# agent-mother.net
KiCad netlist of a schematic drawn in Altium Designer
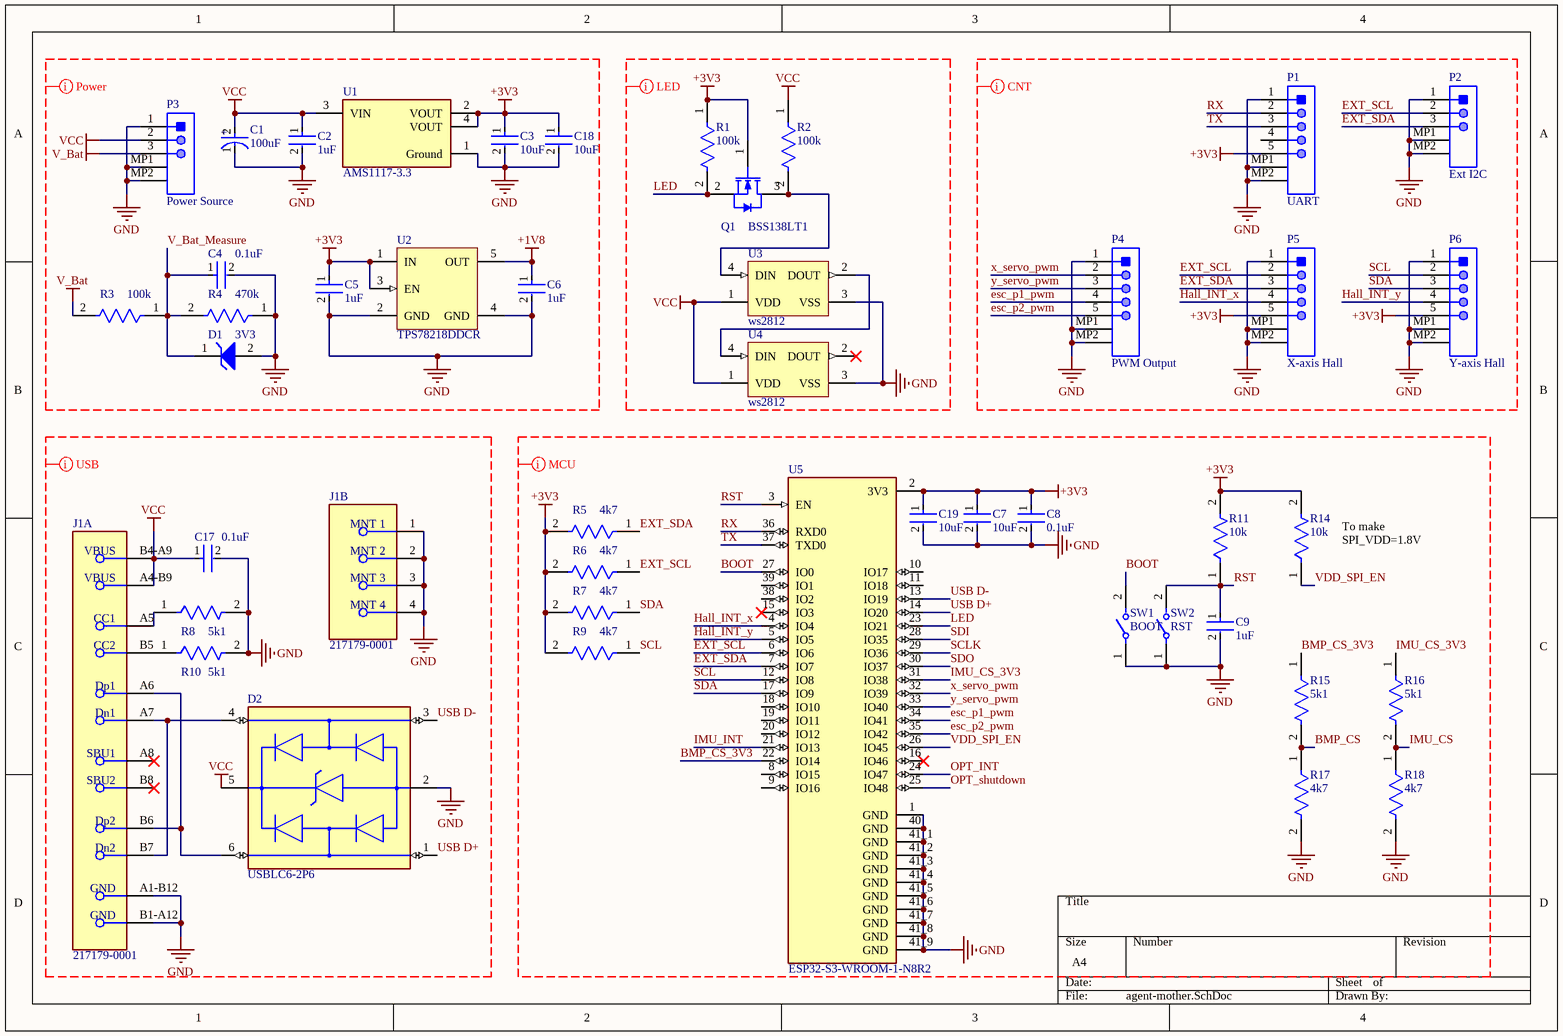
[diagram p0: agent-mother.SchDoc]

(export (version "E")
  (design (tool "Eeschema 10.0.6"))
  (components
    (comp (ref "C1")
      (value "100uF")
      (footprint "FP-T495D107K016ATE125-MFG")
      (description "CAP TANT 100UF 10% 16V 2917")
      (fields (field (name "VOLTAGE") "16V") (field (name "TOLERANCE") "10%"))
      (libsource (lib "Altium Content Vault") (part "a00bbbee19879c290e62620ae7e47b1"))
    )
    (comp (ref "C2")
      (value "1uF")
      (footprint "FP-C0402-BB-MFG")
      (description "CAP CER 1uF 16V X7R 0402")
      (fields
        (field (name "TOLERANCE") "0.1")
        (field (name "OCTOPART") "https://octopart.com/c0402c104k4ractu-kemet-94158")
      )
      (libsource (lib "Altium Content Vault") (part "b4654b650e69147ec39a6b967a45e02"))
    )
    (comp (ref "C3")
      (value "10uF")
      (footprint "FP-C0402-BB-MFG")
      (description "CAP CER 22uF 16V X7R 0402")
      (fields
        (field (name "TOLERANCE") "0.1")
        (field (name "OCTOPART") "https://octopart.com/c0402c104k4ractu-kemet-94158")
      )
      (libsource (lib "Altium Content Vault") (part "b4654b650e69147ec39a6b967a45e02"))
    )
    (comp (ref "C4")
      (value "0.1uF")
      (footprint "FP-C0402-BB-MFG")
      (description "CAP CER 0.1uF 16V X7R 0402")
      (fields
        (field (name "TOLERANCE") "0.1")
        (field (name "OCTOPART") "https://octopart.com/c0402c104k4ractu-kemet-94158")
      )
      (libsource (lib "Altium Content Vault") (part "b4654b650e69147ec39a6b967a45e02"))
    )
    (comp (ref "C5")
      (value "1uF")
      (footprint "FP-C0402-BB-MFG")
      (description "CAP CER 1uF 16V X7R 0402")
      (fields
        (field (name "TOLERANCE") "0.1")
        (field (name "OCTOPART") "https://octopart.com/c0402c104k4ractu-kemet-94158")
      )
      (libsource (lib "Altium Content Vault") (part "b4654b650e69147ec39a6b967a45e02"))
    )
    (comp (ref "C6")
      (value "1uF")
      (footprint "FP-C0402-BB-MFG")
      (description "CAP CER 1uF 16V X7R 0402")
      (fields
        (field (name "TOLERANCE") "0.1")
        (field (name "OCTOPART") "https://octopart.com/c0402c104k4ractu-kemet-94158")
      )
      (libsource (lib "Altium Content Vault") (part "b4654b650e69147ec39a6b967a45e02"))
    )
    (comp (ref "C7")
      (value "10uF")
      (footprint "FP-C0402-BB-MFG")
      (description "CAP CER 22uF 16V X7R 0402")
      (fields
        (field (name "TOLERANCE") "0.1")
        (field (name "OCTOPART") "https://octopart.com/c0402c104k4ractu-kemet-94158")
      )
      (libsource (lib "Altium Content Vault") (part "b4654b650e69147ec39a6b967a45e02"))
    )
    (comp (ref "C8")
      (value "0.1uF")
      (footprint "FP-C0402-BB-MFG")
      (description "CAP CER 0.1uF 16V X7R 0402")
      (fields
        (field (name "TOLERANCE") "0.1")
        (field (name "OCTOPART") "https://octopart.com/c0402c104k4ractu-kemet-94158")
      )
      (libsource (lib "Altium Content Vault") (part "b4654b650e69147ec39a6b967a45e02"))
    )
    (comp (ref "C9")
      (value "1uF")
      (footprint "FP-C0402-BB-MFG")
      (description "CAP CER 1uF 16V X7R 0402")
      (fields
        (field (name "TOLERANCE") "0.1")
        (field (name "OCTOPART") "https://octopart.com/c0402c104k4ractu-kemet-94158")
      )
      (libsource (lib "Altium Content Vault") (part "b4654b650e69147ec39a6b967a45e02"))
    )
    (comp (ref "C17")
      (value "0.1uF")
      (footprint "FP-C0402-BB-MFG")
      (description "CAP CER 0.1uF 16V X7R 0402")
      (fields
        (field (name "TOLERANCE") "0.1")
        (field (name "OCTOPART") "https://octopart.com/c0402c104k4ractu-kemet-94158")
      )
      (libsource (lib "Altium Content Vault") (part "b4654b650e69147ec39a6b967a45e02"))
    )
    (comp (ref "C18")
      (value "10uF")
      (footprint "FP-C0402-BB-MFG")
      (description "CAP CER 22uF 16V X7R 0402")
      (fields
        (field (name "TOLERANCE") "0.1")
        (field (name "OCTOPART") "https://octopart.com/c0402c104k4ractu-kemet-94158")
      )
      (libsource (lib "Altium Content Vault") (part "b4654b650e69147ec39a6b967a45e02"))
    )
    (comp (ref "C19")
      (value "10uF")
      (footprint "FP-C0402-BB-MFG")
      (description "CAP CER 22uF 16V X7R 0402")
      (fields
        (field (name "TOLERANCE") "0.1")
        (field (name "OCTOPART") "https://octopart.com/c0402c104k4ractu-kemet-94158")
      )
      (libsource (lib "Altium Content Vault") (part "b4654b650e69147ec39a6b967a45e02"))
    )
    (comp (ref "D1")
      (value "3V3")
      (footprint "ONSC-SOD-323-2-477-02_V")
      (description "Zener Voltage Regulator, 300 mW, 2-Pin SOD-323, Pb-Free, Tape and Reel")
      (fields (field (name "PARTNUMBER") "MM3Z3V3T1G") (field (name "MANUFACTURER") "On Semiconductor"))
      (libsource (lib "Altium Content Vault") (part "ONSC-K1A2-2"))
    )
    (comp (ref "D2")
      (value "USBLC6-2P6")
      (footprint "SOT-23-6 USBLC6")
      (description "TVS DIODE 5.25V 17V SOT666")
      (libsource (lib "TVMD") (part "USBLC6-2P6"))
    )
    (comp (ref "J1")
      (value "217179-0001")
      (footprint "FP-217179-0001-MFG")
      (description "CONN RCP USB2.0 TYP C 24P SMD RA")
      (libsource (lib "Altium Content Vault") (part "5f86746d156db037abd23105bb3dbc5"))
    )
    (comp (ref "P1")
      (value "UART")
      (footprint "MOLX-52361-0571-5_V")
      (description "Male Header, Pitch 1.25 mm, 1 x 5 Position, Height 3.4 mm, RoHS, Tape and Reel")
      (fields (field (name "MANUFACTURER") "Molex"))
      (libsource (lib "Altium Content Vault") (part "CN-1P-2M-R5"))
    )
    (comp (ref "P2")
      (value "Ext I2C")
      (footprint "FP-53261-0371-MFG")
      (description "CONN HEADER SMD R/A 3POS 1.25MM")
      (fields
        (field (name "MANUFACTURER") "Molex")
        (field (name "OCTOPART") "https://octopart.com/53261-0371-molex-655314")
      )
      (libsource (lib "Components - 19.08.23 - 20.17") (part "CMP-04776-000071-1"))
    )
    (comp (ref "P3")
      (value "Power Source")
      (footprint "FP-53261-0371-MFG")
      (description "CONN HEADER SMD R/A 3POS 1.25MM")
      (fields
        (field (name "MANUFACTURER") "Molex")
        (field (name "OCTOPART") "https://octopart.com/53261-0371-molex-655314")
      )
      (libsource (lib "Components - 19.08.23 - 20.17") (part "CMP-04776-000071-1"))
    )
    (comp (ref "P4")
      (value "PWM Output")
      (footprint "MOLX-52361-0571-5_V")
      (description "Male Header, Pitch 1.25 mm, 1 x 5 Position, Height 3.4 mm, RoHS, Tape and Reel")
      (fields (field (name "MANUFACTURER") "Molex"))
      (libsource (lib "Altium Content Vault") (part "CN-1P-2M-R5"))
    )
    (comp (ref "P5")
      (value "X-axis Hall")
      (footprint "MOLX-52361-0571-5_V")
      (description "Male Header, Pitch 1.25 mm, 1 x 5 Position, Height 3.4 mm, RoHS, Tape and Reel")
      (fields (field (name "MANUFACTURER") "Molex"))
      (libsource (lib "Altium Content Vault") (part "CN-1P-2M-R5"))
    )
    (comp (ref "P6")
      (value "Y-axis Hall")
      (footprint "MOLX-52361-0571-5_V")
      (description "Male Header, Pitch 1.25 mm, 1 x 5 Position, Height 3.4 mm, RoHS, Tape and Reel")
      (fields (field (name "MANUFACTURER") "Molex"))
      (libsource (lib "Altium Content Vault") (part "CN-1P-2M-R5"))
    )
    (comp (ref "Q1")
      (value "BSS138LT1")
      (footprint "ONSC-SOT-23-3-318-08_V")
      (description "Power MOSFET, BSS138LT1, 200 mA, 50 V, N-Channel, 3-Pin SOT-23, Tape and Reel")
      (fields (field (name "MANUFACTURER") "On Semiconductor"))
      (libsource (lib "Altium Content Vault") (part "ONSC-NMOS-G1S2D3-3"))
    )
    (comp (ref "R1")
      (value "100k")
      (footprint "FP-CRCW0402-e3-IPC_A")
      (description "RES Thick Film, 100kΩ, 0.063W, 0402")
      (fields (field (name "TOLERANCE") "5%"))
      (libsource (lib "Altium Content Vault") (part "1029c3af85768c4190bb7ad29bc67b5"))
    )
    (comp (ref "R2")
      (value "100k")
      (footprint "FP-CRCW0402-e3-IPC_A")
      (description "RES Thick Film, 100kΩ, 0.063W, 0402")
      (fields (field (name "TOLERANCE") "5%"))
      (libsource (lib "Altium Content Vault") (part "1029c3af85768c4190bb7ad29bc67b5"))
    )
    (comp (ref "R3")
      (value "100k")
      (footprint "FP-CRCW0402-e3-IPC_A")
      (description "RES Thick Film, 100kΩ, 0.063W, 0402")
      (fields (field (name "TOLERANCE") "5%"))
      (libsource (lib "Altium Content Vault") (part "1029c3af85768c4190bb7ad29bc67b5"))
    )
    (comp (ref "R4")
      (value "470k")
      (footprint "FP-CRCW0402-e3-IPC_A")
      (description "RES Thick Film, 470kΩ, 0.063W, 0402")
      (fields (field (name "TOLERANCE") "5%"))
      (libsource (lib "Altium Content Vault") (part "1029c3af85768c4190bb7ad29bc67b5"))
    )
    (comp (ref "R5")
      (value "4k7")
      (footprint "FP-CRCW0402-e3-IPC_A")
      (description "RES Thick Film, 4k7Ω, 0.063W, 0402")
      (fields (field (name "TOLERANCE") "5%"))
      (libsource (lib "Altium Content Vault") (part "1029c3af85768c4190bb7ad29bc67b5"))
    )
    (comp (ref "R6")
      (value "4k7")
      (footprint "FP-CRCW0402-e3-IPC_A")
      (description "RES Thick Film, 4k7Ω, 0.063W, 0402")
      (fields (field (name "TOLERANCE") "5%"))
      (libsource (lib "Altium Content Vault") (part "1029c3af85768c4190bb7ad29bc67b5"))
    )
    (comp (ref "R7")
      (value "4k7")
      (footprint "FP-CRCW0402-e3-IPC_A")
      (description "RES Thick Film, 4k7Ω, 0.063W, 0402")
      (fields (field (name "TOLERANCE") "5%"))
      (libsource (lib "Altium Content Vault") (part "1029c3af85768c4190bb7ad29bc67b5"))
    )
    (comp (ref "R8")
      (value "5k1")
      (footprint "FP-CRCW0402-e3-IPC_A")
      (description "RES Thick Film, 5k1Ω, 0.063W, 0402")
      (fields (field (name "TOLERANCE") "5%"))
      (libsource (lib "Altium Content Vault") (part "1029c3af85768c4190bb7ad29bc67b5"))
    )
    (comp (ref "R9")
      (value "4k7")
      (footprint "FP-CRCW0402-e3-IPC_A")
      (description "RES Thick Film, 4k7Ω, 0.063W, 0402")
      (fields (field (name "TOLERANCE") "5%"))
      (libsource (lib "Altium Content Vault") (part "1029c3af85768c4190bb7ad29bc67b5"))
    )
    (comp (ref "R10")
      (value "5k1")
      (footprint "FP-CRCW0402-e3-IPC_A")
      (description "RES Thick Film, 5k1Ω, 0.063W, 0402")
      (fields (field (name "TOLERANCE") "5%"))
      (libsource (lib "Altium Content Vault") (part "1029c3af85768c4190bb7ad29bc67b5"))
    )
    (comp (ref "R11")
      (value "10k")
      (footprint "FP-CRCW0402-e3-IPC_A")
      (description "RES Thick Film, 10kΩ, 0.063W, 0402")
      (fields (field (name "TOLERANCE") "5%"))
      (libsource (lib "Altium Content Vault") (part "1029c3af85768c4190bb7ad29bc67b5"))
    )
    (comp (ref "R14")
      (value "10k")
      (footprint "FP-CRCW0402-e3-IPC_A")
      (description "RES Thick Film, 10kΩ, 0.063W, 0402")
      (fields (field (name "TOLERANCE") "5%"))
      (libsource (lib "Altium Content Vault") (part "1029c3af85768c4190bb7ad29bc67b5"))
    )
    (comp (ref "R15")
      (value "5k1")
      (footprint "FP-CRCW0402-e3-IPC_A")
      (description "RES Thick Film, 4k7Ω, 0.063W, 0402")
      (fields (field (name "TOLERANCE") "5%"))
      (libsource (lib "Altium Content Vault") (part "1029c3af85768c4190bb7ad29bc67b5"))
    )
    (comp (ref "R16")
      (value "5k1")
      (footprint "FP-CRCW0402-e3-IPC_A")
      (description "RES Thick Film, 4k7Ω, 0.063W, 0402")
      (fields (field (name "TOLERANCE") "5%"))
      (libsource (lib "Altium Content Vault") (part "1029c3af85768c4190bb7ad29bc67b5"))
    )
    (comp (ref "R17")
      (value "4k7")
      (footprint "FP-CRCW0402-e3-IPC_A")
      (description "RES Thick Film, 4k7Ω, 0.063W, 0402")
      (fields (field (name "TOLERANCE") "5%"))
      (libsource (lib "Altium Content Vault") (part "1029c3af85768c4190bb7ad29bc67b5"))
    )
    (comp (ref "R18")
      (value "4k7")
      (footprint "FP-CRCW0402-e3-IPC_A")
      (description "RES Thick Film, 4k7Ω, 0.063W, 0402")
      (fields (field (name "TOLERANCE") "5%"))
      (libsource (lib "Altium Content Vault") (part "1029c3af85768c4190bb7ad29bc67b5"))
    )
    (comp (ref "SW1")
      (value "BOOT")
      (footprint "FP-B3U-1000P-B-MFG")
      (description "SWITCH TACTILE SPST-NO 0.05A 12V")
      (fields
        (field (name "MANUFACTURER PART NUMBER") "B3U-1000P-B")
        (field (name "OCTOPART") "https://octopart.com/b3u-1000p-b-omron-1057356")
      )
      (libsource (lib "Altium Content Vault") (part "bb27bde45df87f1f469753f287ef5ae"))
    )
    (comp (ref "SW2")
      (value "RST")
      (footprint "FP-B3U-1000P-B-MFG")
      (description "SWITCH TACTILE SPST-NO 0.05A 12V")
      (fields
        (field (name "MANUFACTURER PART NUMBER") "B3U-1000P-B")
        (field (name "OCTOPART") "https://octopart.com/b3u-1000p-b-omron-1057356")
      )
      (libsource (lib "Altium Content Vault") (part "bb27bde45df87f1f469753f287ef5ae"))
    )
    (comp (ref "U1")
      (value "AMS1117-3.3")
      (footprint "FP-AMS1117-IPC_A")
      (description "LDO Voltage Regulators 1A, 3.3V")
      (fields
        (field (name "OCTOPART") "https://octopart.com/ams1117-3.3-advanced+monolithic+systems-25899300")
        (field (name "MANUFACTURER") "Advanced Monolithic Systems")
      )
      (libsource (lib "Altium Content Vault") (part "8bdbb5f8e77002000e30dd2845d0354"))
    )
    (comp (ref "U2")
      (value "TPS78218DDCR")
      (footprint "SOT-23-OT5_M")
      (fields (field (name "MANUFACTURER") "Texas Instruments") (field (name "PARTNUMBER") "TPS78218DRVR"))
      (libsource (lib "TVMD") (part "TI-TPS782XXDRV6-1600X1000TP"))
    )
    (comp (ref "U3")
      (value "ws2812")
      (footprint "ADA-RGB-1655_V")
      (fields (field (name "MANUFACTURER") "Adafruit-Industries-LLC"))
      (libsource (lib "Altium Content Vault") (part "ADA-RGB-1655-4"))
    )
    (comp (ref "U4")
      (value "ws2812")
      (footprint "ADA-RGB-1655_V")
      (fields (field (name "MANUFACTURER") "Adafruit-Industries-LLC"))
      (libsource (lib "Altium Content Vault") (part "ADA-RGB-1655-4"))
    )
    (comp (ref "U5")
      (value "ESP32-S3-WROOM-1-N8R2")
      (footprint "XCVR_ESP32S3WROOM1N8R8")
      (description "Bluetooth, WiFi 802.11b/g/n, Bluetooth v5.0 Transceiver Module 2.4GHz PCB Trace Surface Mount")
      (fields (field (name "MF") "Espressif Systems") (field (name "MP") "ESP32-S3-WROOM-1-N8R8"))
      (libsource (lib "ESP32-S3-WROOM-1-N8R8") (part "ESP32-S3-WROOM-1-N8R8"))
    )
  )
  (nets
    (net (code "1") (name "+1V8") (class "Default")
      (node (ref "C6") (pin "1") (pinfunction "1_1") (pintype "passive"))
      (node (ref "U2") (pin "5") (pinfunction "OUT_5") (pintype "power_in"))
    )
    (net (code "2") (name "+3V3") (class "Default")
      (node (ref "C18") (pin "1") (pinfunction "1_1") (pintype "passive"))
      (node (ref "C19") (pin "1") (pinfunction "1_1") (pintype "passive"))
      (node (ref "C3") (pin "1") (pinfunction "1_1") (pintype "passive"))
      (node (ref "C5") (pin "1") (pinfunction "1_1") (pintype "passive"))
      (node (ref "C7") (pin "1") (pinfunction "1_1") (pintype "passive"))
      (node (ref "C8") (pin "1") (pinfunction "1_1") (pintype "passive"))
      (node (ref "P1") (pin "5") (pinfunction "5_5") (pintype "passive"))
      (node (ref "P5") (pin "5") (pinfunction "5_5") (pintype "passive"))
      (node (ref "P6") (pin "5") (pinfunction "5_5") (pintype "passive"))
      (node (ref "Q1") (pin "1") (pinfunction "G_1") (pintype "passive"))
      (node (ref "R1") (pin "1") (pinfunction "1_1") (pintype "passive"))
      (node (ref "R11") (pin "2") (pinfunction "2_2") (pintype "passive"))
      (node (ref "R14") (pin "2") (pinfunction "2_2") (pintype "passive"))
      (node (ref "R5") (pin "2") (pinfunction "2_2") (pintype "passive"))
      (node (ref "R6") (pin "2") (pinfunction "2_2") (pintype "passive"))
      (node (ref "R7") (pin "2") (pinfunction "2_2") (pintype "passive"))
      (node (ref "R9") (pin "2") (pinfunction "2_2") (pintype "passive"))
      (node (ref "U1") (pin "2") (pinfunction "VOUT_2") (pintype "passive"))
      (node (ref "U1") (pin "4") (pinfunction "VOUT_4") (pintype "passive"))
      (node (ref "U2") (pin "1") (pinfunction "IN_1") (pintype "power_in"))
      (node (ref "U2") (pin "3") (pinfunction "EN_3") (pintype "input"))
      (node (ref "U5") (pin "2") (pinfunction "3V3_2") (pintype "power_in"))
    )
    (net (code "3") (name "/BMP_CS") (class "Default")
      (node (ref "R15") (pin "2") (pinfunction "2_2") (pintype "passive"))
      (node (ref "R17") (pin "1") (pinfunction "1_1") (pintype "passive"))
    )
    (net (code "4") (name "/BMP_CS_3V3") (class "Default")
      (node (ref "R15") (pin "1") (pinfunction "1_1") (pintype "passive"))
      (node (ref "U5") (pin "22") (pinfunction "IO14_22") (pintype "bidirectional"))
    )
    (net (code "5") (name "/BOOT") (class "Default")
      (node (ref "SW1") (pin "2") (pinfunction "2_2") (pintype "passive"))
      (node (ref "U5") (pin "27") (pinfunction "IO0_27") (pintype "bidirectional"))
    )
    (net (code "6") (name "/EXT_SCL") (class "Default")
      (node (ref "P2") (pin "2") (pinfunction "2_2") (pintype "passive"))
      (node (ref "P5") (pin "2") (pinfunction "2_2") (pintype "passive"))
      (node (ref "R6") (pin "1") (pinfunction "1_1") (pintype "passive"))
      (node (ref "U5") (pin "6") (pinfunction "IO6_6") (pintype "bidirectional"))
    )
    (net (code "7") (name "/EXT_SDA") (class "Default")
      (node (ref "P2") (pin "3") (pinfunction "3_3") (pintype "passive"))
      (node (ref "P5") (pin "3") (pinfunction "3_3") (pintype "passive"))
      (node (ref "R5") (pin "1") (pinfunction "1_1") (pintype "passive"))
      (node (ref "U5") (pin "7") (pinfunction "IO7_7") (pintype "bidirectional"))
    )
    (net (code "8") (name "/Hall_INT_x") (class "Default")
      (node (ref "P5") (pin "4") (pinfunction "4_4") (pintype "passive"))
      (node (ref "U5") (pin "4") (pinfunction "IO4_4") (pintype "bidirectional"))
    )
    (net (code "9") (name "/Hall_INT_y") (class "Default")
      (node (ref "P6") (pin "4") (pinfunction "4_4") (pintype "passive"))
      (node (ref "U5") (pin "5") (pinfunction "IO5_5") (pintype "bidirectional"))
    )
    (net (code "10") (name "/IMU_CS") (class "Default")
      (node (ref "R16") (pin "2") (pinfunction "2_2") (pintype "passive"))
      (node (ref "R18") (pin "1") (pinfunction "1_1") (pintype "passive"))
    )
    (net (code "11") (name "/IMU_CS_3V3") (class "Default")
      (node (ref "R16") (pin "1") (pinfunction "1_1") (pintype "passive"))
      (node (ref "U5") (pin "31") (pinfunction "IO38_31") (pintype "bidirectional"))
    )
    (net (code "12") (name "/IMU_INT") (class "Default")
      (node (ref "U5") (pin "21") (pinfunction "IO13_21") (pintype "bidirectional"))
    )
    (net (code "13") (name "/LED") (class "Default")
      (node (ref "Q1") (pin "2") (pinfunction "S_2") (pintype "passive"))
      (node (ref "R1") (pin "2") (pinfunction "2_2") (pintype "passive"))
      (node (ref "U5") (pin "23") (pinfunction "IO21_23") (pintype "bidirectional"))
    )
    (net (code "14") (name "/OPT_INT") (class "Default")
      (node (ref "U5") (pin "24") (pinfunction "IO47_24") (pintype "bidirectional"))
    )
    (net (code "15") (name "/OPT_shutdown") (class "Default")
      (node (ref "U5") (pin "25") (pinfunction "IO48_25") (pintype "bidirectional"))
    )
    (net (code "16") (name "/RST") (class "Default")
      (node (ref "C9") (pin "1") (pinfunction "1_1") (pintype "passive"))
      (node (ref "R11") (pin "1") (pinfunction "1_1") (pintype "passive"))
      (node (ref "SW2") (pin "2") (pinfunction "2_2") (pintype "passive"))
      (node (ref "U5") (pin "3") (pinfunction "EN_3") (pintype "input"))
    )
    (net (code "17") (name "/RX") (class "Default")
      (node (ref "P1") (pin "2") (pinfunction "2_2") (pintype "passive"))
      (node (ref "U5") (pin "36") (pinfunction "RXD0_36") (pintype "bidirectional"))
    )
    (net (code "18") (name "/SCL") (class "Default")
      (node (ref "P6") (pin "2") (pinfunction "2_2") (pintype "passive"))
      (node (ref "R9") (pin "1") (pinfunction "1_1") (pintype "passive"))
      (node (ref "U5") (pin "12") (pinfunction "IO8_12") (pintype "bidirectional"))
    )
    (net (code "19") (name "/SCLK") (class "Default")
      (node (ref "U5") (pin "29") (pinfunction "IO36_29") (pintype "bidirectional"))
    )
    (net (code "20") (name "/SDA") (class "Default")
      (node (ref "P6") (pin "3") (pinfunction "3_3") (pintype "passive"))
      (node (ref "R7") (pin "1") (pinfunction "1_1") (pintype "passive"))
      (node (ref "U5") (pin "17") (pinfunction "IO9_17") (pintype "bidirectional"))
    )
    (net (code "21") (name "/SDI") (class "Default")
      (node (ref "U5") (pin "28") (pinfunction "IO35_28") (pintype "bidirectional"))
    )
    (net (code "22") (name "/SDO") (class "Default")
      (node (ref "U5") (pin "30") (pinfunction "IO37_30") (pintype "bidirectional"))
    )
    (net (code "23") (name "/TX") (class "Default")
      (node (ref "P1") (pin "3") (pinfunction "3_3") (pintype "passive"))
      (node (ref "U5") (pin "37") (pinfunction "TXD0_37") (pintype "bidirectional"))
    )
    (net (code "24") (name "/USB D+") (class "Default")
      (node (ref "D2") (pin "1") (pinfunction "I/O1_1") (pintype "bidirectional"))
      (node (ref "U5") (pin "14") (pinfunction "IO20_14") (pintype "bidirectional"))
    )
    (net (code "25") (name "/USB D-") (class "Default")
      (node (ref "D2") (pin "3") (pinfunction "I/O2_3") (pintype "bidirectional"))
      (node (ref "U5") (pin "13") (pinfunction "IO19_13") (pintype "bidirectional"))
    )
    (net (code "26") (name "/VDD_SPI_EN") (class "Default")
      (node (ref "R14") (pin "1") (pinfunction "1_1") (pintype "passive"))
      (node (ref "U5") (pin "26") (pinfunction "IO45_26") (pintype "bidirectional"))
    )
    (net (code "27") (name "/V_Bat_Measure") (class "Default")
      (node (ref "C4") (pin "1") (pinfunction "1_1") (pintype "passive"))
      (node (ref "D1") (pin "1") (pinfunction "K_1") (pintype "passive"))
      (node (ref "R3") (pin "1") (pinfunction "1_1") (pintype "passive"))
      (node (ref "R4") (pin "2") (pinfunction "2_2") (pintype "passive"))
    )
    (net (code "28") (name "/esc_p1_pwm") (class "Default")
      (node (ref "P4") (pin "4") (pinfunction "4_4") (pintype "passive"))
      (node (ref "U5") (pin "34") (pinfunction "IO41_34") (pintype "bidirectional"))
    )
    (net (code "29") (name "/esc_p2_pwm") (class "Default")
      (node (ref "P4") (pin "5") (pinfunction "5_5") (pintype "passive"))
      (node (ref "U5") (pin "35") (pinfunction "IO42_35") (pintype "bidirectional"))
    )
    (net (code "30") (name "/x_servo_pwm") (class "Default")
      (node (ref "P4") (pin "2") (pinfunction "2_2") (pintype "passive"))
      (node (ref "U5") (pin "32") (pinfunction "IO39_32") (pintype "bidirectional"))
    )
    (net (code "31") (name "/y_servo_pwm") (class "Default")
      (node (ref "P4") (pin "3") (pinfunction "3_3") (pintype "passive"))
      (node (ref "U5") (pin "33") (pinfunction "IO40_33") (pintype "bidirectional"))
    )
    (net (code "32") (name "GND") (class "Default")
      (node (ref "C1") (pin "1") (pinfunction "C_1") (pintype "passive"))
      (node (ref "C17") (pin "2") (pinfunction "2_2") (pintype "passive"))
      (node (ref "C18") (pin "2") (pinfunction "2_2") (pintype "passive"))
      (node (ref "C19") (pin "2") (pinfunction "2_2") (pintype "passive"))
      (node (ref "C2") (pin "2") (pinfunction "2_2") (pintype "passive"))
      (node (ref "C3") (pin "2") (pinfunction "2_2") (pintype "passive"))
      (node (ref "C4") (pin "2") (pinfunction "2_2") (pintype "passive"))
      (node (ref "C5") (pin "2") (pinfunction "2_2") (pintype "passive"))
      (node (ref "C6") (pin "2") (pinfunction "2_2") (pintype "passive"))
      (node (ref "C7") (pin "2") (pinfunction "2_2") (pintype "passive"))
      (node (ref "C8") (pin "2") (pinfunction "2_2") (pintype "passive"))
      (node (ref "C9") (pin "2") (pinfunction "2_2") (pintype "passive"))
      (node (ref "D1") (pin "2") (pinfunction "A_2") (pintype "passive"))
      (node (ref "D2") (pin "2") (pinfunction "GND_2") (pintype "power_in"))
      (node (ref "J1") (pin "1") (pinfunction "MNT_1_1") (pintype "passive"))
      (node (ref "J1") (pin "2") (pinfunction "MNT_2_2") (pintype "passive"))
      (node (ref "J1") (pin "3") (pinfunction "MNT_3_3") (pintype "passive"))
      (node (ref "J1") (pin "4") (pinfunction "MNT_4_4") (pintype "passive"))
      (node (ref "J1") (pin "A1-B12") (pinfunction "GND_A1-B12") (pintype "power_in"))
      (node (ref "J1") (pin "B1-A12") (pinfunction "GND_B1-A12") (pintype "power_in"))
      (node (ref "P1") (pin "1") (pinfunction "1_1") (pintype "passive"))
      (node (ref "P1") (pin "MP1") (pinfunction "MP1_MP1") (pintype "passive"))
      (node (ref "P1") (pin "MP2") (pinfunction "MP2_MP2") (pintype "passive"))
      (node (ref "P2") (pin "1") (pinfunction "1_1") (pintype "passive"))
      (node (ref "P2") (pin "MP1") (pinfunction "MP1_MP1") (pintype "passive"))
      (node (ref "P2") (pin "MP2") (pinfunction "MP2_MP2") (pintype "passive"))
      (node (ref "P3") (pin "1") (pinfunction "1_1") (pintype "passive"))
      (node (ref "P3") (pin "MP1") (pinfunction "MP1_MP1") (pintype "passive"))
      (node (ref "P3") (pin "MP2") (pinfunction "MP2_MP2") (pintype "passive"))
      (node (ref "P4") (pin "1") (pinfunction "1_1") (pintype "passive"))
      (node (ref "P4") (pin "MP1") (pinfunction "MP1_MP1") (pintype "passive"))
      (node (ref "P4") (pin "MP2") (pinfunction "MP2_MP2") (pintype "passive"))
      (node (ref "P5") (pin "1") (pinfunction "1_1") (pintype "passive"))
      (node (ref "P5") (pin "MP1") (pinfunction "MP1_MP1") (pintype "passive"))
      (node (ref "P5") (pin "MP2") (pinfunction "MP2_MP2") (pintype "passive"))
      (node (ref "P6") (pin "1") (pinfunction "1_1") (pintype "passive"))
      (node (ref "P6") (pin "MP1") (pinfunction "MP1_MP1") (pintype "passive"))
      (node (ref "P6") (pin "MP2") (pinfunction "MP2_MP2") (pintype "passive"))
      (node (ref "R10") (pin "2") (pinfunction "2_2") (pintype "passive"))
      (node (ref "R17") (pin "2") (pinfunction "2_2") (pintype "passive"))
      (node (ref "R18") (pin "2") (pinfunction "2_2") (pintype "passive"))
      (node (ref "R4") (pin "1") (pinfunction "1_1") (pintype "passive"))
      (node (ref "R8") (pin "2") (pinfunction "2_2") (pintype "passive"))
      (node (ref "SW1") (pin "1") (pinfunction "1_1") (pintype "passive"))
      (node (ref "SW2") (pin "1") (pinfunction "1_1") (pintype "passive"))
      (node (ref "U1") (pin "1") (pinfunction "Ground_1") (pintype "power_in"))
      (node (ref "U2") (pin "2") (pinfunction "GND_2") (pintype "power_in"))
      (node (ref "U2") (pin "4") (pinfunction "GND_4") (pintype "power_in"))
      (node (ref "U3") (pin "3") (pinfunction "VSS_3") (pintype "power_in"))
      (node (ref "U4") (pin "3") (pinfunction "VSS_3") (pintype "power_in"))
      (node (ref "U5") (pin "1") (pinfunction "GND_1") (pintype "power_in"))
      (node (ref "U5") (pin "40") (pinfunction "GND_40") (pintype "power_in"))
      (node (ref "U5") (pin "41_1") (pinfunction "GND_41_1") (pintype "power_in"))
      (node (ref "U5") (pin "41_2") (pinfunction "GND_41_2") (pintype "power_in"))
      (node (ref "U5") (pin "41_3") (pinfunction "GND_41_3") (pintype "power_in"))
      (node (ref "U5") (pin "41_4") (pinfunction "GND_41_4") (pintype "power_in"))
      (node (ref "U5") (pin "41_5") (pinfunction "GND_41_5") (pintype "power_in"))
      (node (ref "U5") (pin "41_6") (pinfunction "GND_41_6") (pintype "power_in"))
      (node (ref "U5") (pin "41_7") (pinfunction "GND_41_7") (pintype "power_in"))
      (node (ref "U5") (pin "41_8") (pinfunction "GND_41_8") (pintype "power_in"))
      (node (ref "U5") (pin "41_9") (pinfunction "GND_41_9") (pintype "power_in"))
    )
    (net (code "33") (name "Net-(J1A-CC1)") (class "Default")
      (node (ref "J1") (pin "A5") (pinfunction "CC1_A5") (pintype "passive"))
      (node (ref "R8") (pin "1") (pinfunction "1_1") (pintype "passive"))
    )
    (net (code "34") (name "Net-(J1A-CC2)") (class "Default")
      (node (ref "J1") (pin "B5") (pinfunction "CC2_B5") (pintype "passive"))
      (node (ref "R10") (pin "1") (pinfunction "1_1") (pintype "passive"))
    )
    (net (code "35") (name "Net-(J1A-Dn1)") (class "Default")
      (node (ref "D2") (pin "4") (pinfunction "I/O2_4") (pintype "bidirectional"))
      (node (ref "J1") (pin "A7") (pinfunction "Dn1_A7") (pintype "passive"))
      (node (ref "J1") (pin "B7") (pinfunction "Dn2_B7") (pintype "passive"))
    )
    (net (code "36") (name "Net-(J1A-Dp1)") (class "Default")
      (node (ref "D2") (pin "6") (pinfunction "I/O1_6") (pintype "bidirectional"))
      (node (ref "J1") (pin "A6") (pinfunction "Dp1_A6") (pintype "passive"))
      (node (ref "J1") (pin "B6") (pinfunction "Dp2_B6") (pintype "passive"))
    )
    (net (code "37") (name "Net-(Q1-D)") (class "Default")
      (node (ref "Q1") (pin "3") (pinfunction "D_3") (pintype "passive"))
      (node (ref "R2") (pin "2") (pinfunction "2_2") (pintype "passive"))
      (node (ref "U3") (pin "4") (pinfunction "DIN_4") (pintype "input"))
    )
    (net (code "38") (name "Net-(U3-DOUT)") (class "Default")
      (node (ref "U3") (pin "2") (pinfunction "DOUT_2") (pintype "output"))
      (node (ref "U4") (pin "4") (pinfunction "DIN_4") (pintype "input"))
    )
    (net (code "39") (name "VCC") (class "Default")
      (node (ref "C1") (pin "2") (pinfunction "A_2") (pintype "passive"))
      (node (ref "C17") (pin "1") (pinfunction "1_1") (pintype "passive"))
      (node (ref "C2") (pin "1") (pinfunction "1_1") (pintype "passive"))
      (node (ref "D2") (pin "5") (pinfunction "VBUS_5") (pintype "power_in"))
      (node (ref "J1") (pin "A4-B9") (pinfunction "VBUS_A4-B9") (pintype "power_in"))
      (node (ref "J1") (pin "B4-A9") (pinfunction "VBUS_B4-A9") (pintype "power_in"))
      (node (ref "P3") (pin "2") (pinfunction "2_2") (pintype "passive"))
      (node (ref "R2") (pin "1") (pinfunction "1_1") (pintype "passive"))
      (node (ref "U1") (pin "3") (pinfunction "VIN_3") (pintype "power_in"))
      (node (ref "U3") (pin "1") (pinfunction "VDD_1") (pintype "power_in"))
      (node (ref "U4") (pin "1") (pinfunction "VDD_1") (pintype "power_in"))
    )
    (net (code "40") (name "V_Bat") (class "Default")
      (node (ref "P3") (pin "3") (pinfunction "3_3") (pintype "passive"))
      (node (ref "R3") (pin "2") (pinfunction "2_2") (pintype "passive"))
    )
    (net (code "41") (name "unconnected-(J1A-SBU1-PadA8)") (class "Default")
      (node (ref "J1") (pin "A8") (pinfunction "SBU1_A8") (pintype "passive+no_connect"))
    )
    (net (code "42") (name "unconnected-(J1A-SBU2-PadB8)") (class "Default")
      (node (ref "J1") (pin "B8") (pinfunction "SBU2_B8") (pintype "passive+no_connect"))
    )
    (net (code "43") (name "unconnected-(P1-Pad4)") (class "Default")
      (node (ref "P1") (pin "4") (pinfunction "4_4") (pintype "passive"))
    )
    (net (code "44") (name "unconnected-(U4-DOUT-Pad2)") (class "Default")
      (node (ref "U4") (pin "2") (pinfunction "DOUT_2") (pintype "output+no_connect"))
    )
    (net (code "45") (name "unconnected-(U5-IO1-Pad39)") (class "Default")
      (node (ref "U5") (pin "39") (pinfunction "IO1_39") (pintype "bidirectional"))
    )
    (net (code "46") (name "unconnected-(U5-IO2-Pad38)") (class "Default")
      (node (ref "U5") (pin "38") (pinfunction "IO2_38") (pintype "bidirectional"))
    )
    (net (code "47") (name "unconnected-(U5-IO3-Pad15)") (class "Default")
      (node (ref "U5") (pin "15") (pinfunction "IO3_15") (pintype "bidirectional+no_connect"))
    )
    (net (code "48") (name "unconnected-(U5-IO10-Pad18)") (class "Default")
      (node (ref "U5") (pin "18") (pinfunction "IO10_18") (pintype "bidirectional"))
    )
    (net (code "49") (name "unconnected-(U5-IO11-Pad19)") (class "Default")
      (node (ref "U5") (pin "19") (pinfunction "IO11_19") (pintype "bidirectional"))
    )
    (net (code "50") (name "unconnected-(U5-IO12-Pad20)") (class "Default")
      (node (ref "U5") (pin "20") (pinfunction "IO12_20") (pintype "bidirectional"))
    )
    (net (code "51") (name "unconnected-(U5-IO15-Pad8)") (class "Default")
      (node (ref "U5") (pin "8") (pinfunction "IO15_8") (pintype "bidirectional"))
    )
    (net (code "52") (name "unconnected-(U5-IO16-Pad9)") (class "Default")
      (node (ref "U5") (pin "9") (pinfunction "IO16_9") (pintype "bidirectional"))
    )
    (net (code "53") (name "unconnected-(U5-IO17-Pad10)") (class "Default")
      (node (ref "U5") (pin "10") (pinfunction "IO17_10") (pintype "bidirectional"))
    )
    (net (code "54") (name "unconnected-(U5-IO18-Pad11)") (class "Default")
      (node (ref "U5") (pin "11") (pinfunction "IO18_11") (pintype "bidirectional"))
    )
    (net (code "55") (name "unconnected-(U5-IO46-Pad16)") (class "Default")
      (node (ref "U5") (pin "16") (pinfunction "IO46_16") (pintype "bidirectional+no_connect"))
    )
  )
)
